# RC_Transmitter_TX_FINAL_v43.net
KiCad netlist of a schematic drawn in EAGLE
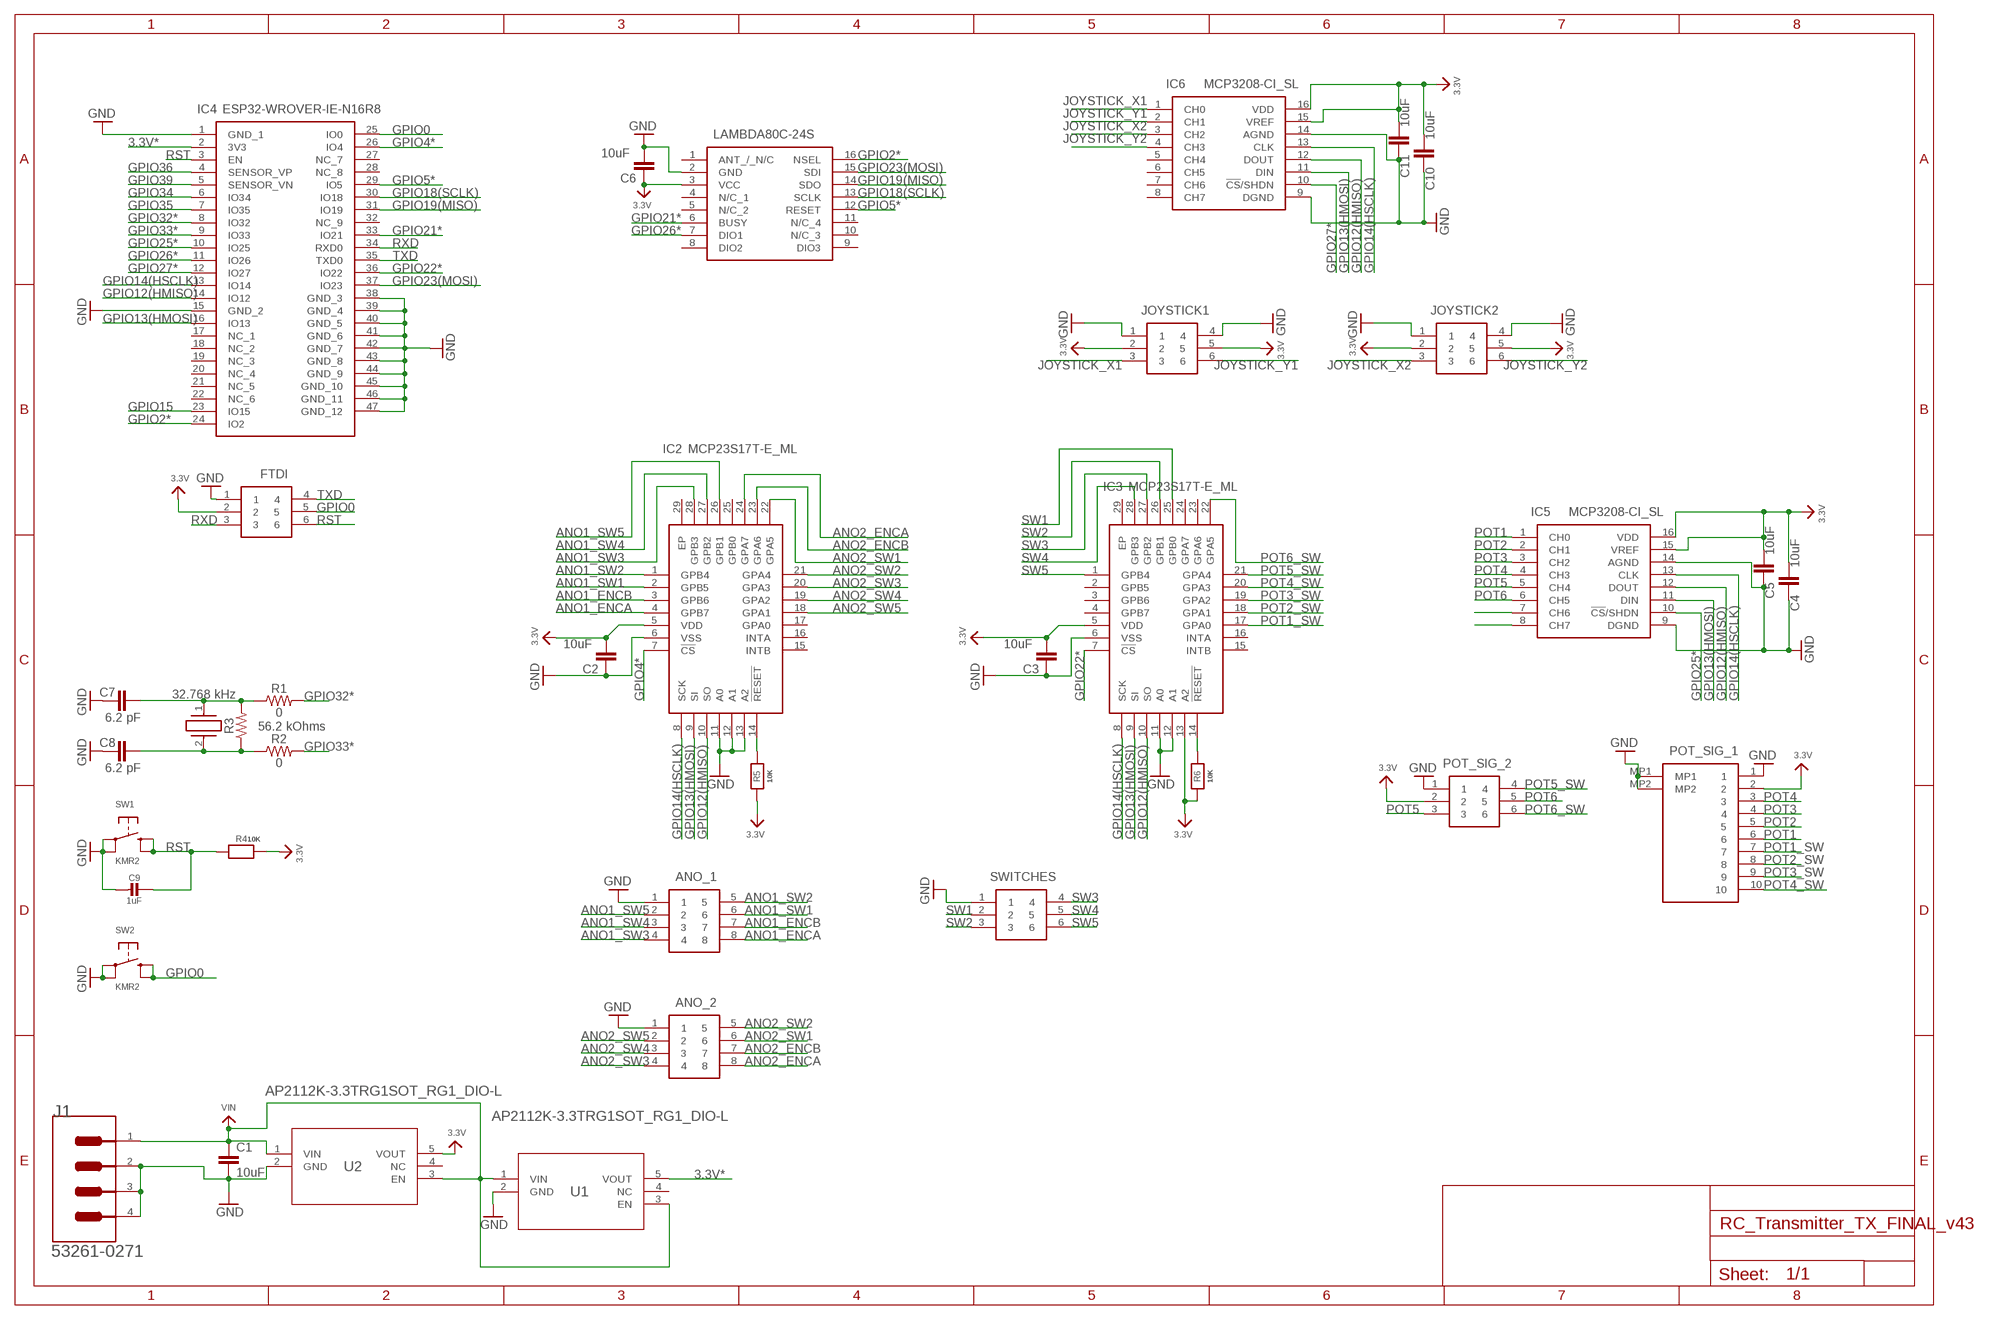
[diagram p0: schematic, sheet 1]

(export (version "E")
  (design (tool "Eeschema 10.0.6"))
  (components
    (comp (ref "ANO_1")
      (value "0532610871")
      (footprint "eagle-import:53261-0871")
      (libsource (lib "eagle-import") (part "0532610871"))
    )
    (comp (ref "ANO_2")
      (value "0532610871")
      (footprint "eagle-import:53261-0871")
      (libsource (lib "eagle-import") (part "0532610871"))
    )
    (comp (ref "C1")
      (value "10uF")
      (footprint "eagle-import:0805")
      (libsource (lib "eagle-import") (part "10UF-0805-10V-10%"))
    )
    (comp (ref "C2")
      (value "10uF")
      (footprint "eagle-import:0805")
      (libsource (lib "eagle-import") (part "10UF-0805-10V-10%"))
    )
    (comp (ref "C3")
      (value "10uF")
      (footprint "eagle-import:0805")
      (libsource (lib "eagle-import") (part "10UF-0805-10V-10%"))
    )
    (comp (ref "C4")
      (value "10uF")
      (footprint "eagle-import:0805")
      (libsource (lib "eagle-import") (part "10UF-0805-10V-10%"))
    )
    (comp (ref "C5")
      (value "10uF")
      (footprint "eagle-import:0805")
      (libsource (lib "eagle-import") (part "10UF-0805-10V-10%"))
    )
    (comp (ref "C6")
      (value "10uF")
      (footprint "eagle-import:0805")
      (libsource (lib "eagle-import") (part "10UF-0805-10V-10%"))
    )
    (comp (ref "C7")
      (value "6.2 pF")
      (footprint "eagle-import:CAPC2012X110")
      (libsource (lib "eagle-import") (part "CCHIP-0805(2012-METRIC)_"))
    )
    (comp (ref "C8")
      (value "6.2 pF")
      (footprint "eagle-import:CAPC2012X110")
      (libsource (lib "eagle-import") (part "CCHIP-0805(2012-METRIC)_"))
    )
    (comp (ref "C9")
      (value "1uF")
      (footprint "eagle-import:0805-NO")
      (libsource (lib "eagle-import") (part "CAP_CERAMIC0805-NOOUTLINE"))
    )
    (comp (ref "C10")
      (value "10uF")
      (footprint "eagle-import:0805")
      (libsource (lib "eagle-import") (part "10UF-0805-10V-10%"))
    )
    (comp (ref "C11")
      (value "10uF")
      (footprint "eagle-import:0805")
      (libsource (lib "eagle-import") (part "10UF-0805-10V-10%"))
    )
    (comp (ref "CRYSTAL")
      (value "32.768 kHz")
      (footprint "eagle-import:ECX327CDX1293")
      (fields
        (field (name "ARROW_PART_NUMBER") "ECX-.327-CDX-1293")
        (field (name "MOUSER_PART_NUMBER") "520-ECX-.327CDX-1293")
        (field (name "ARROW_PART_NUMBER_1") "Crystal")
      )
      (libsource (lib "eagle-import") (part "ECX-.327-CDX-1293"))
    )
    (comp (ref "FTDI")
      (value "0532610671")
      (footprint "eagle-import:0532610671")
      (libsource (lib "eagle-import") (part "0532610671"))
    )
    (comp (ref "IC1")
      (value "LAMBDA80C-24S")
      (footprint "eagle-import:LAMBDA80C24S")
      (fields (field (name "MOUSER_PART_NUMBER") "223-LAMBDA80C-24S"))
      (libsource (lib "eagle-import") (part "LAMBDA80C-24S"))
    )
    (comp (ref "IC2")
      (value "MCP23S17T-E_ML")
      (footprint "eagle-import:QFN65P600X600X100-29N")
      (fields
        (field (name "ARROW_PART_NUMBER") "MCP23S17T-E/ML")
        (field (name "MOUSER_PART_NUMBER") "579-MCP23S17T-E/ML")
      )
      (libsource (lib "eagle-import") (part "MCP23S17T-E_ML"))
    )
    (comp (ref "IC3")
      (value "MCP23S17T-E_ML")
      (footprint "eagle-import:QFN65P600X600X100-29N")
      (fields
        (field (name "ARROW_PART_NUMBER") "MCP23S17T-E/ML")
        (field (name "MOUSER_PART_NUMBER") "579-MCP23S17T-E/ML")
      )
      (libsource (lib "eagle-import") (part "MCP23S17T-E_ML"))
    )
    (comp (ref "IC4")
      (value "ESP32-WROVER-IE-N16R8")
      (footprint "eagle-import:ESP32WROVERIEN16R8")
      (fields
        (field (name "MANUFACTURER_PART_NUMBER") "ESP32-Wrover-IE-N16R8")
        (field (name "MOUSER_PART_NUMBER") "356-ESP32WRVIE2864UC")
      )
      (libsource (lib "eagle-import") (part "ESP32-WROVER-IE-N16R8"))
    )
    (comp (ref "IC5")
      (value "MCP3208-CI_SL")
      (footprint "eagle-import:SOIC127P600X175-16N")
      (fields
        (field (name "ARROW_PART_NUMBER") "MCP3208-CI/SL")
        (field (name "MOUSER_PART_NUMBER") "579-MCP3208CISL")
      )
      (libsource (lib "eagle-import") (part "MCP3208-CI_SL"))
    )
    (comp (ref "IC6")
      (value "MCP3208-CI_SL")
      (footprint "eagle-import:SOIC127P600X175-16N")
      (fields
        (field (name "ARROW_PART_NUMBER") "MCP3208-CI/SL")
        (field (name "MOUSER_PART_NUMBER") "579-MCP3208CISL")
      )
      (libsource (lib "eagle-import") (part "MCP3208-CI_SL"))
    )
    (comp (ref "J1")
      (value "MOLEX_53261-0271MOLEX_53261-0271_0_0")
      (footprint "eagle-import:MOLEX_53261-0271_0")
      (fields
        (field (name "DIGIKEY_PART_NUMBER") "WM7620CT-ND")
        (field (name "MF") "Molex")
        (field (name "MOUSER_PART_NUMBER") "538-53261-0271")
      )
      (libsource (lib "eagle-import") (part "MOLEX_53261-0271MOLEX_53261-0271_0_0"))
    )
    (comp (ref "JOYSTICK1")
      (value "0532610671")
      (footprint "eagle-import:0532610671")
      (libsource (lib "eagle-import") (part "0532610671"))
    )
    (comp (ref "JOYSTICK2")
      (value "0532610671")
      (footprint "eagle-import:0532610671")
      (libsource (lib "eagle-import") (part "0532610671"))
    )
    (comp (ref "POT_SIG_1")
      (value "0532611071")
      (footprint "eagle-import:0532611071")
      (libsource (lib "eagle-import") (part "0532611071"))
    )
    (comp (ref "POT_SIG_2")
      (value "0532610671")
      (footprint "eagle-import:0532610671")
      (libsource (lib "eagle-import") (part "0532610671"))
    )
    (comp (ref "R1")
      (value "0")
      (footprint "eagle-import:0603")
      (libsource (lib "eagle-import") (part "0OHM-0603-1/10W-5%"))
    )
    (comp (ref "R2")
      (value "0")
      (footprint "eagle-import:0603")
      (libsource (lib "eagle-import") (part "0OHM-0603-1/10W-5%"))
    )
    (comp (ref "R3")
      (value "56.2 kOhms")
      (footprint "eagle-import:0603")
      (libsource (lib "eagle-import") (part "0OHM-0603-1/10W-5%"))
    )
    (comp (ref "R4")
      (value "10K")
      (footprint "eagle-import:_0805")
      (libsource (lib "eagle-import") (part "RESISTOR_0805"))
    )
    (comp (ref "R5")
      (value "10K")
      (footprint "eagle-import:_0805")
      (libsource (lib "eagle-import") (part "RESISTOR_0805"))
    )
    (comp (ref "R6")
      (value "10K")
      (footprint "eagle-import:_0805")
      (libsource (lib "eagle-import") (part "RESISTOR_0805"))
    )
    (comp (ref "SW1")
      (value "KMR2")
      (footprint "eagle-import:BTN_KMR2_4.6X2.8")
      (libsource (lib "eagle-import") (part "SWITCH_TACT_SMT4.6X2.8"))
    )
    (comp (ref "SW2")
      (value "KMR2")
      (footprint "eagle-import:BTN_KMR2_4.6X2.8")
      (libsource (lib "eagle-import") (part "SWITCH_TACT_SMT4.6X2.8"))
    )
    (comp (ref "SWITCHES")
      (value "0532610671")
      (footprint "eagle-import:0532610671")
      (libsource (lib "eagle-import") (part "0532610671"))
    )
    (comp (ref "U1")
      (value "AP2112K-3.3TRG1SOT_RG1_DIO-L")
      (footprint "eagle-import:SOT_RG1_DIO-L")
      (fields
        (field (name "MANUFACTURER_PART_NUMBER") "AP2112K-3.3TRG1")
        (field (name "COPYRIGHT") "Copyright (C) 2023 Ultra Librarian. All rights reserved.")
      )
      (libsource (lib "eagle-import") (part "AP2112K-3.3TRG1SOT_RG1_DIO-L"))
    )
    (comp (ref "U2")
      (value "AP2112K-3.3TRG1SOT_RG1_DIO-L")
      (footprint "eagle-import:SOT_RG1_DIO-L")
      (fields
        (field (name "MANUFACTURER_PART_NUMBER") "AP2112K-3.3TRG1")
        (field (name "COPYRIGHT") "Copyright (C) 2023 Ultra Librarian. All rights reserved.")
      )
      (libsource (lib "eagle-import") (part "AP2112K-3.3TRG1SOT_RG1_DIO-L"))
    )
  )
  (nets
    (net (code "1") (name "/3.3V*") (class "Default")
      (node (ref "IC4") (pin "2") (pinfunction "3V3_2") (pintype "bidirectional"))
      (node (ref "U1") (pin "5") (pinfunction "VOUT_5") (pintype "passive"))
    )
    (net (code "2") (name "/ANO1_ENCA") (class "Default")
      (node (ref "ANO_1") (pin "8") (pinfunction "8_8") (pintype "bidirectional"))
      (node (ref "IC2") (pin "4") (pinfunction "GPB7_4") (pintype "bidirectional"))
    )
    (net (code "3") (name "/ANO1_ENCB") (class "Default")
      (node (ref "ANO_1") (pin "7") (pinfunction "7_7") (pintype "bidirectional"))
      (node (ref "IC2") (pin "3") (pinfunction "GPB6_3") (pintype "bidirectional"))
    )
    (net (code "4") (name "/ANO1_SW1") (class "Default")
      (node (ref "ANO_1") (pin "6") (pinfunction "6_6") (pintype "bidirectional"))
      (node (ref "IC2") (pin "2") (pinfunction "GPB5_2") (pintype "bidirectional"))
    )
    (net (code "5") (name "/ANO1_SW2") (class "Default")
      (node (ref "ANO_1") (pin "5") (pinfunction "5_5") (pintype "bidirectional"))
      (node (ref "IC2") (pin "1") (pinfunction "GPB4_1") (pintype "bidirectional"))
    )
    (net (code "6") (name "/ANO1_SW3") (class "Default")
      (node (ref "ANO_1") (pin "4") (pinfunction "4_4") (pintype "bidirectional"))
      (node (ref "IC2") (pin "28") (pinfunction "GPB3_28") (pintype "bidirectional"))
    )
    (net (code "7") (name "/ANO1_SW4") (class "Default")
      (node (ref "ANO_1") (pin "3") (pinfunction "3_3") (pintype "bidirectional"))
      (node (ref "IC2") (pin "27") (pinfunction "GPB2_27") (pintype "bidirectional"))
    )
    (net (code "8") (name "/ANO1_SW5") (class "Default")
      (node (ref "ANO_1") (pin "2") (pinfunction "2_2") (pintype "bidirectional"))
      (node (ref "IC2") (pin "26") (pinfunction "GPB1_26") (pintype "bidirectional"))
    )
    (net (code "9") (name "/ANO2_ENCA") (class "Default")
      (node (ref "ANO_2") (pin "8") (pinfunction "8_8") (pintype "bidirectional"))
      (node (ref "IC2") (pin "24") (pinfunction "GPA7_24") (pintype "bidirectional"))
    )
    (net (code "10") (name "/ANO2_ENCB") (class "Default")
      (node (ref "ANO_2") (pin "7") (pinfunction "7_7") (pintype "bidirectional"))
      (node (ref "IC2") (pin "23") (pinfunction "GPA6_23") (pintype "bidirectional"))
    )
    (net (code "11") (name "/ANO2_SW1") (class "Default")
      (node (ref "ANO_2") (pin "6") (pinfunction "6_6") (pintype "bidirectional"))
      (node (ref "IC2") (pin "22") (pinfunction "GPA5_22") (pintype "bidirectional"))
    )
    (net (code "12") (name "/ANO2_SW2") (class "Default")
      (node (ref "ANO_2") (pin "5") (pinfunction "5_5") (pintype "bidirectional"))
      (node (ref "IC2") (pin "21") (pinfunction "GPA4_21") (pintype "bidirectional"))
    )
    (net (code "13") (name "/ANO2_SW3") (class "Default")
      (node (ref "ANO_2") (pin "4") (pinfunction "4_4") (pintype "bidirectional"))
      (node (ref "IC2") (pin "20") (pinfunction "GPA3_20") (pintype "bidirectional"))
    )
    (net (code "14") (name "/ANO2_SW4") (class "Default")
      (node (ref "ANO_2") (pin "3") (pinfunction "3_3") (pintype "bidirectional"))
      (node (ref "IC2") (pin "19") (pinfunction "GPA2_19") (pintype "bidirectional"))
    )
    (net (code "15") (name "/ANO2_SW5") (class "Default")
      (node (ref "ANO_2") (pin "2") (pinfunction "2_2") (pintype "bidirectional"))
      (node (ref "IC2") (pin "18") (pinfunction "GPA1_18") (pintype "bidirectional"))
    )
    (net (code "16") (name "/GPIO0") (class "Default")
      (node (ref "FTDI") (pin "5") (pinfunction "5_5") (pintype "bidirectional"))
      (node (ref "IC4") (pin "25") (pinfunction "IO0_25") (pintype "bidirectional"))
      (node (ref "SW2") (pin "B") (pinfunction "S_B") (pintype "passive"))
      (node (ref "SW2") (pin "B'") (pinfunction "S1_B'") (pintype "passive"))
    )
    (net (code "17") (name "/GPIO2*") (class "Default")
      (node (ref "IC1") (pin "16") (pinfunction "NSEL_16") (pintype "bidirectional"))
      (node (ref "IC4") (pin "24") (pinfunction "IO2_24") (pintype "bidirectional"))
    )
    (net (code "18") (name "/GPIO4*") (class "Default")
      (node (ref "IC2") (pin "7") (pinfunction "~{CS}_7") (pintype "bidirectional"))
      (node (ref "IC4") (pin "26") (pinfunction "IO4_26") (pintype "bidirectional"))
    )
    (net (code "19") (name "/GPIO5*") (class "Default")
      (node (ref "IC1") (pin "12") (pinfunction "RESET_12") (pintype "bidirectional"))
      (node (ref "IC4") (pin "29") (pinfunction "IO5_29") (pintype "bidirectional"))
    )
    (net (code "20") (name "/GPIO12(HMISO)") (class "Default")
      (node (ref "IC2") (pin "10") (pinfunction "SO_10") (pintype "bidirectional"))
      (node (ref "IC3") (pin "10") (pinfunction "SO_10") (pintype "bidirectional"))
      (node (ref "IC4") (pin "14") (pinfunction "IO12_14") (pintype "bidirectional"))
      (node (ref "IC5") (pin "12") (pinfunction "DOUT_12") (pintype "bidirectional"))
      (node (ref "IC6") (pin "12") (pinfunction "DOUT_12") (pintype "bidirectional"))
    )
    (net (code "21") (name "/GPIO13(HMOSI)") (class "Default")
      (node (ref "IC2") (pin "9") (pinfunction "SI_9") (pintype "bidirectional"))
      (node (ref "IC3") (pin "9") (pinfunction "SI_9") (pintype "bidirectional"))
      (node (ref "IC4") (pin "16") (pinfunction "IO13_16") (pintype "bidirectional"))
      (node (ref "IC5") (pin "11") (pinfunction "DIN_11") (pintype "bidirectional"))
      (node (ref "IC6") (pin "11") (pinfunction "DIN_11") (pintype "bidirectional"))
    )
    (net (code "22") (name "/GPIO14(HSCLK)") (class "Default")
      (node (ref "IC2") (pin "8") (pinfunction "SCK_8") (pintype "bidirectional"))
      (node (ref "IC3") (pin "8") (pinfunction "SCK_8") (pintype "bidirectional"))
      (node (ref "IC4") (pin "13") (pinfunction "IO14_13") (pintype "bidirectional"))
      (node (ref "IC5") (pin "13") (pinfunction "CLK_13") (pintype "bidirectional"))
      (node (ref "IC6") (pin "13") (pinfunction "CLK_13") (pintype "bidirectional"))
    )
    (net (code "23") (name "/GPIO15") (class "Default")
      (node (ref "IC4") (pin "23") (pinfunction "IO15_23") (pintype "bidirectional"))
    )
    (net (code "24") (name "/GPIO18(SCLK)") (class "Default")
      (node (ref "IC1") (pin "13") (pinfunction "SCLK_13") (pintype "bidirectional"))
      (node (ref "IC4") (pin "30") (pinfunction "IO18_30") (pintype "bidirectional"))
    )
    (net (code "25") (name "/GPIO19(MISO)") (class "Default")
      (node (ref "IC1") (pin "14") (pinfunction "SDO_14") (pintype "bidirectional"))
      (node (ref "IC4") (pin "31") (pinfunction "IO19_31") (pintype "bidirectional"))
    )
    (net (code "26") (name "/GPIO21*") (class "Default")
      (node (ref "IC1") (pin "6") (pinfunction "BUSY_6") (pintype "bidirectional"))
      (node (ref "IC4") (pin "33") (pinfunction "IO21_33") (pintype "bidirectional"))
    )
    (net (code "27") (name "/GPIO22*") (class "Default")
      (node (ref "IC3") (pin "7") (pinfunction "~{CS}_7") (pintype "bidirectional"))
      (node (ref "IC4") (pin "36") (pinfunction "IO22_36") (pintype "bidirectional"))
    )
    (net (code "28") (name "/GPIO23(MOSI)") (class "Default")
      (node (ref "IC1") (pin "15") (pinfunction "SDI_15") (pintype "bidirectional"))
      (node (ref "IC4") (pin "37") (pinfunction "IO23_37") (pintype "bidirectional"))
    )
    (net (code "29") (name "/GPIO25*") (class "Default")
      (node (ref "IC4") (pin "10") (pinfunction "IO25_10") (pintype "bidirectional"))
      (node (ref "IC5") (pin "10") (pinfunction "~{CS}/SHDN_10") (pintype "bidirectional"))
    )
    (net (code "30") (name "/GPIO26*") (class "Default")
      (node (ref "IC1") (pin "7") (pinfunction "DIO1_7") (pintype "bidirectional"))
      (node (ref "IC4") (pin "11") (pinfunction "IO26_11") (pintype "bidirectional"))
    )
    (net (code "31") (name "/GPIO27*") (class "Default")
      (node (ref "IC4") (pin "12") (pinfunction "IO27_12") (pintype "bidirectional"))
      (node (ref "IC6") (pin "10") (pinfunction "~{CS}/SHDN_10") (pintype "bidirectional"))
    )
    (net (code "32") (name "/GPIO32*") (class "Default")
      (node (ref "IC4") (pin "8") (pinfunction "IO32_8") (pintype "bidirectional"))
      (node (ref "R1") (pin "2") (pinfunction "2_2") (pintype "passive"))
    )
    (net (code "33") (name "/GPIO33*") (class "Default")
      (node (ref "IC4") (pin "9") (pinfunction "IO33_9") (pintype "bidirectional"))
      (node (ref "R2") (pin "2") (pinfunction "2_2") (pintype "passive"))
    )
    (net (code "34") (name "/GPIO34") (class "Default")
      (node (ref "IC4") (pin "6") (pinfunction "IO34_6") (pintype "bidirectional"))
    )
    (net (code "35") (name "/GPIO35") (class "Default")
      (node (ref "IC4") (pin "7") (pinfunction "IO35_7") (pintype "bidirectional"))
    )
    (net (code "36") (name "/GPIO36") (class "Default")
      (node (ref "IC4") (pin "4") (pinfunction "SENSOR_VP_4") (pintype "bidirectional"))
    )
    (net (code "37") (name "/GPIO39") (class "Default")
      (node (ref "IC4") (pin "5") (pinfunction "SENSOR_VN_5") (pintype "bidirectional"))
    )
    (net (code "38") (name "/JOYSTICK_X1") (class "Default")
      (node (ref "IC6") (pin "1") (pinfunction "CH0_1") (pintype "bidirectional"))
      (node (ref "JOYSTICK1") (pin "3") (pinfunction "3_3") (pintype "bidirectional"))
    )
    (net (code "39") (name "/JOYSTICK_X2") (class "Default")
      (node (ref "IC6") (pin "3") (pinfunction "CH2_3") (pintype "bidirectional"))
      (node (ref "JOYSTICK2") (pin "3") (pinfunction "3_3") (pintype "bidirectional"))
    )
    (net (code "40") (name "/JOYSTICK_Y1") (class "Default")
      (node (ref "IC6") (pin "2") (pinfunction "CH1_2") (pintype "bidirectional"))
      (node (ref "JOYSTICK1") (pin "6") (pinfunction "6_6") (pintype "bidirectional"))
    )
    (net (code "41") (name "/JOYSTICK_Y2") (class "Default")
      (node (ref "IC6") (pin "4") (pinfunction "CH3_4") (pintype "bidirectional"))
      (node (ref "JOYSTICK2") (pin "6") (pinfunction "6_6") (pintype "bidirectional"))
    )
    (net (code "42") (name "/POT1") (class "Default")
      (node (ref "IC5") (pin "1") (pinfunction "CH0_1") (pintype "bidirectional"))
      (node (ref "POT_SIG_1") (pin "6") (pinfunction "6_6") (pintype "bidirectional"))
    )
    (net (code "43") (name "/POT1_SW") (class "Default")
      (node (ref "IC3") (pin "17") (pinfunction "GPA0_17") (pintype "bidirectional"))
      (node (ref "POT_SIG_1") (pin "7") (pinfunction "7_7") (pintype "bidirectional"))
    )
    (net (code "44") (name "/POT2") (class "Default")
      (node (ref "IC5") (pin "2") (pinfunction "CH1_2") (pintype "bidirectional"))
      (node (ref "POT_SIG_1") (pin "5") (pinfunction "5_5") (pintype "bidirectional"))
    )
    (net (code "45") (name "/POT2_SW") (class "Default")
      (node (ref "IC3") (pin "18") (pinfunction "GPA1_18") (pintype "bidirectional"))
      (node (ref "POT_SIG_1") (pin "8") (pinfunction "8_8") (pintype "bidirectional"))
    )
    (net (code "46") (name "/POT3") (class "Default")
      (node (ref "IC5") (pin "3") (pinfunction "CH2_3") (pintype "bidirectional"))
      (node (ref "POT_SIG_1") (pin "4") (pinfunction "4_4") (pintype "bidirectional"))
    )
    (net (code "47") (name "/POT3_SW") (class "Default")
      (node (ref "IC3") (pin "19") (pinfunction "GPA2_19") (pintype "bidirectional"))
      (node (ref "POT_SIG_1") (pin "9") (pinfunction "9_9") (pintype "bidirectional"))
    )
    (net (code "48") (name "/POT4") (class "Default")
      (node (ref "IC5") (pin "4") (pinfunction "CH3_4") (pintype "bidirectional"))
      (node (ref "POT_SIG_1") (pin "3") (pinfunction "3_3") (pintype "bidirectional"))
    )
    (net (code "49") (name "/POT4_SW") (class "Default")
      (node (ref "IC3") (pin "20") (pinfunction "GPA3_20") (pintype "bidirectional"))
      (node (ref "POT_SIG_1") (pin "10") (pinfunction "10_10") (pintype "bidirectional"))
    )
    (net (code "50") (name "/POT5") (class "Default")
      (node (ref "IC5") (pin "5") (pinfunction "CH4_5") (pintype "bidirectional"))
      (node (ref "POT_SIG_2") (pin "3") (pinfunction "3_3") (pintype "bidirectional"))
    )
    (net (code "51") (name "/POT5_SW") (class "Default")
      (node (ref "IC3") (pin "21") (pinfunction "GPA4_21") (pintype "bidirectional"))
      (node (ref "POT_SIG_2") (pin "4") (pinfunction "4_4") (pintype "bidirectional"))
    )
    (net (code "52") (name "/POT6") (class "Default")
      (node (ref "IC5") (pin "6") (pinfunction "CH5_6") (pintype "bidirectional"))
      (node (ref "POT_SIG_2") (pin "5") (pinfunction "5_5") (pintype "bidirectional"))
    )
    (net (code "53") (name "/POT6_SW") (class "Default")
      (node (ref "IC3") (pin "22") (pinfunction "GPA5_22") (pintype "bidirectional"))
      (node (ref "POT_SIG_2") (pin "6") (pinfunction "6_6") (pintype "bidirectional"))
    )
    (net (code "54") (name "/RST") (class "Default")
      (node (ref "C9") (pin "1") (pinfunction "1_1") (pintype "passive"))
      (node (ref "FTDI") (pin "6") (pinfunction "6_6") (pintype "bidirectional"))
      (node (ref "IC4") (pin "3") (pinfunction "EN_3") (pintype "bidirectional"))
      (node (ref "R4") (pin "1") (pinfunction "1_1") (pintype "passive"))
      (node (ref "SW1") (pin "B") (pinfunction "S_B") (pintype "passive"))
      (node (ref "SW1") (pin "B'") (pinfunction "S1_B'") (pintype "passive"))
    )
    (net (code "55") (name "/RXD") (class "Default")
      (node (ref "FTDI") (pin "3") (pinfunction "3_3") (pintype "bidirectional"))
      (node (ref "IC4") (pin "34") (pinfunction "RXD0_34") (pintype "bidirectional"))
    )
    (net (code "56") (name "/SW1") (class "Default")
      (node (ref "IC3") (pin "25") (pinfunction "GPB0_25") (pintype "bidirectional"))
      (node (ref "SWITCHES") (pin "2") (pinfunction "2_2") (pintype "bidirectional"))
    )
    (net (code "57") (name "/SW2") (class "Default")
      (node (ref "IC3") (pin "26") (pinfunction "GPB1_26") (pintype "bidirectional"))
      (node (ref "SWITCHES") (pin "3") (pinfunction "3_3") (pintype "bidirectional"))
    )
    (net (code "58") (name "/SW3") (class "Default")
      (node (ref "IC3") (pin "27") (pinfunction "GPB2_27") (pintype "bidirectional"))
      (node (ref "SWITCHES") (pin "4") (pinfunction "4_4") (pintype "bidirectional"))
    )
    (net (code "59") (name "/SW4") (class "Default")
      (node (ref "IC3") (pin "28") (pinfunction "GPB3_28") (pintype "bidirectional"))
      (node (ref "SWITCHES") (pin "5") (pinfunction "5_5") (pintype "bidirectional"))
    )
    (net (code "60") (name "/SW5") (class "Default")
      (node (ref "IC3") (pin "1") (pinfunction "GPB4_1") (pintype "bidirectional"))
      (node (ref "SWITCHES") (pin "6") (pinfunction "6_6") (pintype "bidirectional"))
    )
    (net (code "61") (name "/TXD") (class "Default")
      (node (ref "FTDI") (pin "4") (pinfunction "4_4") (pintype "bidirectional"))
      (node (ref "IC4") (pin "35") (pinfunction "TXD0_35") (pintype "bidirectional"))
    )
    (net (code "62") (name "3.3V") (class "Default")
      (node (ref "C10") (pin "2") (pinfunction "2_2") (pintype "passive"))
      (node (ref "C11") (pin "2") (pinfunction "2_2") (pintype "passive"))
      (node (ref "C2") (pin "2") (pinfunction "2_2") (pintype "passive"))
      (node (ref "C3") (pin "2") (pinfunction "2_2") (pintype "passive"))
      (node (ref "C4") (pin "2") (pinfunction "2_2") (pintype "passive"))
      (node (ref "C5") (pin "2") (pinfunction "2_2") (pintype "passive"))
      (node (ref "C6") (pin "1") (pinfunction "1_1") (pintype "passive"))
      (node (ref "FTDI") (pin "2") (pinfunction "2_2") (pintype "bidirectional"))
      (node (ref "IC1") (pin "3") (pinfunction "VCC_3") (pintype "bidirectional"))
      (node (ref "IC2") (pin "5") (pinfunction "VDD_5") (pintype "bidirectional"))
      (node (ref "IC3") (pin "13") (pinfunction "A2_13") (pintype "bidirectional"))
      (node (ref "IC3") (pin "5") (pinfunction "VDD_5") (pintype "bidirectional"))
      (node (ref "IC5") (pin "15") (pinfunction "VREF_15") (pintype "bidirectional"))
      (node (ref "IC5") (pin "16") (pinfunction "VDD_16") (pintype "bidirectional"))
      (node (ref "IC6") (pin "15") (pinfunction "VREF_15") (pintype "bidirectional"))
      (node (ref "IC6") (pin "16") (pinfunction "VDD_16") (pintype "bidirectional"))
      (node (ref "JOYSTICK1") (pin "2") (pinfunction "2_2") (pintype "bidirectional"))
      (node (ref "JOYSTICK1") (pin "5") (pinfunction "5_5") (pintype "bidirectional"))
      (node (ref "JOYSTICK2") (pin "2") (pinfunction "2_2") (pintype "bidirectional"))
      (node (ref "JOYSTICK2") (pin "5") (pinfunction "5_5") (pintype "bidirectional"))
      (node (ref "POT_SIG_1") (pin "2") (pinfunction "2_2") (pintype "bidirectional"))
      (node (ref "POT_SIG_2") (pin "2") (pinfunction "2_2") (pintype "bidirectional"))
      (node (ref "R4") (pin "2") (pinfunction "2_2") (pintype "passive"))
      (node (ref "R5") (pin "1") (pinfunction "1_1") (pintype "passive"))
      (node (ref "R6") (pin "1") (pinfunction "1_1") (pintype "passive"))
      (node (ref "U2") (pin "5") (pinfunction "VOUT_5") (pintype "passive"))
    )
    (net (code "63") (name "GND") (class "Default")
      (node (ref "ANO_1") (pin "1") (pinfunction "1_1") (pintype "bidirectional"))
      (node (ref "ANO_2") (pin "1") (pinfunction "1_1") (pintype "bidirectional"))
      (node (ref "C1") (pin "2") (pinfunction "2_2") (pintype "passive"))
      (node (ref "C10") (pin "1") (pinfunction "1_1") (pintype "passive"))
      (node (ref "C11") (pin "1") (pinfunction "1_1") (pintype "passive"))
      (node (ref "C2") (pin "1") (pinfunction "1_1") (pintype "passive"))
      (node (ref "C3") (pin "1") (pinfunction "1_1") (pintype "passive"))
      (node (ref "C4") (pin "1") (pinfunction "1_1") (pintype "passive"))
      (node (ref "C5") (pin "1") (pinfunction "1_1") (pintype "passive"))
      (node (ref "C6") (pin "2") (pinfunction "2_2") (pintype "passive"))
      (node (ref "C7") (pin "1") (pinfunction "1_1") (pintype "passive"))
      (node (ref "C8") (pin "1") (pinfunction "1_1") (pintype "passive"))
      (node (ref "C9") (pin "2") (pinfunction "2_2") (pintype "passive"))
      (node (ref "FTDI") (pin "1") (pinfunction "1_1") (pintype "bidirectional"))
      (node (ref "IC1") (pin "2") (pinfunction "GND_2") (pintype "bidirectional"))
      (node (ref "IC2") (pin "11") (pinfunction "A0_11") (pintype "bidirectional"))
      (node (ref "IC2") (pin "12") (pinfunction "A1_12") (pintype "bidirectional"))
      (node (ref "IC2") (pin "13") (pinfunction "A2_13") (pintype "bidirectional"))
      (node (ref "IC2") (pin "6") (pinfunction "VSS_6") (pintype "bidirectional"))
      (node (ref "IC3") (pin "11") (pinfunction "A0_11") (pintype "bidirectional"))
      (node (ref "IC3") (pin "12") (pinfunction "A1_12") (pintype "bidirectional"))
      (node (ref "IC3") (pin "6") (pinfunction "VSS_6") (pintype "bidirectional"))
      (node (ref "IC4") (pin "1") (pinfunction "GND_1_1") (pintype "bidirectional"))
      (node (ref "IC4") (pin "15") (pinfunction "GND_2_15") (pintype "bidirectional"))
      (node (ref "IC4") (pin "38") (pinfunction "GND_3_38") (pintype "bidirectional"))
      (node (ref "IC4") (pin "39") (pinfunction "GND_4_39") (pintype "bidirectional"))
      (node (ref "IC4") (pin "40") (pinfunction "GND_5_40") (pintype "bidirectional"))
      (node (ref "IC4") (pin "41") (pinfunction "GND_6_41") (pintype "bidirectional"))
      (node (ref "IC4") (pin "42") (pinfunction "GND_7_42") (pintype "bidirectional"))
      (node (ref "IC4") (pin "43") (pinfunction "GND_8_43") (pintype "bidirectional"))
      (node (ref "IC4") (pin "44") (pinfunction "GND_9_44") (pintype "bidirectional"))
      (node (ref "IC4") (pin "45") (pinfunction "GND_10_45") (pintype "bidirectional"))
      (node (ref "IC4") (pin "46") (pinfunction "GND_11_46") (pintype "bidirectional"))
      (node (ref "IC4") (pin "47") (pinfunction "GND_12_47") (pintype "bidirectional"))
      (node (ref "IC5") (pin "14") (pinfunction "AGND_14") (pintype "bidirectional"))
      (node (ref "IC5") (pin "9") (pinfunction "DGND_9") (pintype "bidirectional"))
      (node (ref "IC6") (pin "14") (pinfunction "AGND_14") (pintype "bidirectional"))
      (node (ref "IC6") (pin "9") (pinfunction "DGND_9") (pintype "bidirectional"))
      (node (ref "J1") (pin "2") (pinfunction "2_2") (pintype "bidirectional"))
      (node (ref "J1") (pin "3") (pinfunction "MNT_1_3") (pintype "bidirectional"))
      (node (ref "J1") (pin "4") (pinfunction "MNT_2_4") (pintype "bidirectional"))
      (node (ref "JOYSTICK1") (pin "1") (pinfunction "1_1") (pintype "bidirectional"))
      (node (ref "JOYSTICK1") (pin "4") (pinfunction "4_4") (pintype "bidirectional"))
      (node (ref "JOYSTICK2") (pin "1") (pinfunction "1_1") (pintype "bidirectional"))
      (node (ref "JOYSTICK2") (pin "4") (pinfunction "4_4") (pintype "bidirectional"))
      (node (ref "POT_SIG_1") (pin "1") (pinfunction "1_1") (pintype "bidirectional"))
      (node (ref "POT_SIG_1") (pin "MP1") (pinfunction "MP1_MP1") (pintype "bidirectional"))
      (node (ref "POT_SIG_1") (pin "MP2") (pinfunction "MP2_MP2") (pintype "bidirectional"))
      (node (ref "POT_SIG_2") (pin "1") (pinfunction "1_1") (pintype "bidirectional"))
      (node (ref "SW1") (pin "A") (pinfunction "P_A") (pintype "passive"))
      (node (ref "SW1") (pin "A'") (pinfunction "P1_A'") (pintype "passive"))
      (node (ref "SW2") (pin "A") (pinfunction "P_A") (pintype "passive"))
      (node (ref "SW2") (pin "A'") (pinfunction "P1_A'") (pintype "passive"))
      (node (ref "SWITCHES") (pin "1") (pinfunction "1_1") (pintype "bidirectional"))
      (node (ref "U1") (pin "2") (pinfunction "GND_2") (pintype "passive"))
      (node (ref "U2") (pin "2") (pinfunction "GND_2") (pintype "passive"))
    )
    (net (code "64") (name "Net-(CRYSTAL-X1)") (class "Default")
      (node (ref "C7") (pin "2") (pinfunction "2_2") (pintype "passive"))
      (node (ref "CRYSTAL") (pin "1") (pinfunction "X1_1") (pintype "bidirectional"))
      (node (ref "R1") (pin "1") (pinfunction "1_1") (pintype "passive"))
      (node (ref "R3") (pin "2") (pinfunction "2_2") (pintype "passive"))
    )
    (net (code "65") (name "Net-(CRYSTAL-X2)") (class "Default")
      (node (ref "C8") (pin "2") (pinfunction "2_2") (pintype "passive"))
      (node (ref "CRYSTAL") (pin "2") (pinfunction "X2_2") (pintype "bidirectional"))
      (node (ref "R2") (pin "1") (pinfunction "1_1") (pintype "passive"))
      (node (ref "R3") (pin "1") (pinfunction "1_1") (pintype "passive"))
    )
    (net (code "66") (name "Net-(IC2-~{RESET})") (class "Default")
      (node (ref "IC2") (pin "14") (pinfunction "~{RESET}_14") (pintype "bidirectional"))
      (node (ref "R5") (pin "2") (pinfunction "2_2") (pintype "passive"))
    )
    (net (code "67") (name "Net-(IC3-~{RESET})") (class "Default")
      (node (ref "IC3") (pin "14") (pinfunction "~{RESET}_14") (pintype "bidirectional"))
      (node (ref "R6") (pin "2") (pinfunction "2_2") (pintype "passive"))
    )
    (net (code "68") (name "VIN") (class "Default")
      (node (ref "C1") (pin "1") (pinfunction "1_1") (pintype "passive"))
      (node (ref "J1") (pin "1") (pinfunction "1_1") (pintype "bidirectional"))
      (node (ref "U1") (pin "1") (pinfunction "VIN_1") (pintype "passive"))
      (node (ref "U1") (pin "3") (pinfunction "EN_3") (pintype "passive"))
      (node (ref "U2") (pin "1") (pinfunction "VIN_1") (pintype "passive"))
      (node (ref "U2") (pin "3") (pinfunction "EN_3") (pintype "passive"))
    )
    (net (code "69") (name "unconnected-(IC1-ANT_{slash}_N{slash}C-Pad1)") (class "Default")
      (node (ref "IC1") (pin "1") (pinfunction "ANT_/_N/C_1") (pintype "bidirectional"))
    )
    (net (code "70") (name "unconnected-(IC1-DIO2-Pad8)") (class "Default")
      (node (ref "IC1") (pin "8") (pinfunction "DIO2_8") (pintype "bidirectional"))
    )
    (net (code "71") (name "unconnected-(IC1-DIO3-Pad9)") (class "Default")
      (node (ref "IC1") (pin "9") (pinfunction "DIO3_9") (pintype "bidirectional"))
    )
    (net (code "72") (name "unconnected-(IC1-N{slash}C_1-Pad4)") (class "Default")
      (node (ref "IC1") (pin "4") (pinfunction "N/C_1_4") (pintype "bidirectional"))
    )
    (net (code "73") (name "unconnected-(IC1-N{slash}C_2-Pad5)") (class "Default")
      (node (ref "IC1") (pin "5") (pinfunction "N/C_2_5") (pintype "bidirectional"))
    )
    (net (code "74") (name "unconnected-(IC1-N{slash}C_3-Pad10)") (class "Default")
      (node (ref "IC1") (pin "10") (pinfunction "N/C_3_10") (pintype "bidirectional"))
    )
    (net (code "75") (name "unconnected-(IC1-N{slash}C_4-Pad11)") (class "Default")
      (node (ref "IC1") (pin "11") (pinfunction "N/C_4_11") (pintype "bidirectional"))
    )
    (net (code "76") (name "unconnected-(IC2-EP-Pad29)") (class "Default")
      (node (ref "IC2") (pin "29") (pinfunction "EP_29") (pintype "bidirectional"))
    )
    (net (code "77") (name "unconnected-(IC2-GPA0-Pad17)") (class "Default")
      (node (ref "IC2") (pin "17") (pinfunction "GPA0_17") (pintype "bidirectional"))
    )
    (net (code "78") (name "unconnected-(IC2-GPB0-Pad25)") (class "Default")
      (node (ref "IC2") (pin "25") (pinfunction "GPB0_25") (pintype "bidirectional"))
    )
    (net (code "79") (name "unconnected-(IC2-INTA-Pad16)") (class "Default")
      (node (ref "IC2") (pin "16") (pinfunction "INTA_16") (pintype "bidirectional"))
    )
    (net (code "80") (name "unconnected-(IC2-INTB-Pad15)") (class "Default")
      (node (ref "IC2") (pin "15") (pinfunction "INTB_15") (pintype "bidirectional"))
    )
    (net (code "81") (name "unconnected-(IC3-EP-Pad29)") (class "Default")
      (node (ref "IC3") (pin "29") (pinfunction "EP_29") (pintype "bidirectional"))
    )
    (net (code "82") (name "unconnected-(IC3-GPA6-Pad23)") (class "Default")
      (node (ref "IC3") (pin "23") (pinfunction "GPA6_23") (pintype "bidirectional"))
    )
    (net (code "83") (name "unconnected-(IC3-GPA7-Pad24)") (class "Default")
      (node (ref "IC3") (pin "24") (pinfunction "GPA7_24") (pintype "bidirectional"))
    )
    (net (code "84") (name "unconnected-(IC3-GPB5-Pad2)") (class "Default")
      (node (ref "IC3") (pin "2") (pinfunction "GPB5_2") (pintype "bidirectional"))
    )
    (net (code "85") (name "unconnected-(IC3-GPB6-Pad3)") (class "Default")
      (node (ref "IC3") (pin "3") (pinfunction "GPB6_3") (pintype "bidirectional"))
    )
    (net (code "86") (name "unconnected-(IC3-GPB7-Pad4)") (class "Default")
      (node (ref "IC3") (pin "4") (pinfunction "GPB7_4") (pintype "bidirectional"))
    )
    (net (code "87") (name "unconnected-(IC3-INTA-Pad16)") (class "Default")
      (node (ref "IC3") (pin "16") (pinfunction "INTA_16") (pintype "bidirectional"))
    )
    (net (code "88") (name "unconnected-(IC3-INTB-Pad15)") (class "Default")
      (node (ref "IC3") (pin "15") (pinfunction "INTB_15") (pintype "bidirectional"))
    )
    (net (code "89") (name "unconnected-(IC4-NC_1-Pad17)") (class "Default")
      (node (ref "IC4") (pin "17") (pinfunction "NC_1_17") (pintype "bidirectional"))
    )
    (net (code "90") (name "unconnected-(IC4-NC_2-Pad18)") (class "Default")
      (node (ref "IC4") (pin "18") (pinfunction "NC_2_18") (pintype "bidirectional"))
    )
    (net (code "91") (name "unconnected-(IC4-NC_3-Pad19)") (class "Default")
      (node (ref "IC4") (pin "19") (pinfunction "NC_3_19") (pintype "bidirectional"))
    )
    (net (code "92") (name "unconnected-(IC4-NC_4-Pad20)") (class "Default")
      (node (ref "IC4") (pin "20") (pinfunction "NC_4_20") (pintype "bidirectional"))
    )
    (net (code "93") (name "unconnected-(IC4-NC_5-Pad21)") (class "Default")
      (node (ref "IC4") (pin "21") (pinfunction "NC_5_21") (pintype "bidirectional"))
    )
    (net (code "94") (name "unconnected-(IC4-NC_6-Pad22)") (class "Default")
      (node (ref "IC4") (pin "22") (pinfunction "NC_6_22") (pintype "bidirectional"))
    )
    (net (code "95") (name "unconnected-(IC4-NC_7-Pad27)") (class "Default")
      (node (ref "IC4") (pin "27") (pinfunction "NC_7_27") (pintype "bidirectional"))
    )
    (net (code "96") (name "unconnected-(IC4-NC_8-Pad28)") (class "Default")
      (node (ref "IC4") (pin "28") (pinfunction "NC_8_28") (pintype "bidirectional"))
    )
    (net (code "97") (name "unconnected-(IC4-NC_9-Pad32)") (class "Default")
      (node (ref "IC4") (pin "32") (pinfunction "NC_9_32") (pintype "bidirectional"))
    )
    (net (code "98") (name "unconnected-(IC5-CH6-Pad7)") (class "Default")
      (node (ref "IC5") (pin "7") (pinfunction "CH6_7") (pintype "bidirectional"))
    )
    (net (code "99") (name "unconnected-(IC5-CH7-Pad8)") (class "Default")
      (node (ref "IC5") (pin "8") (pinfunction "CH7_8") (pintype "bidirectional"))
    )
    (net (code "100") (name "unconnected-(IC6-CH4-Pad5)") (class "Default")
      (node (ref "IC6") (pin "5") (pinfunction "CH4_5") (pintype "bidirectional"))
    )
    (net (code "101") (name "unconnected-(IC6-CH5-Pad6)") (class "Default")
      (node (ref "IC6") (pin "6") (pinfunction "CH5_6") (pintype "bidirectional"))
    )
    (net (code "102") (name "unconnected-(IC6-CH6-Pad7)") (class "Default")
      (node (ref "IC6") (pin "7") (pinfunction "CH6_7") (pintype "bidirectional"))
    )
    (net (code "103") (name "unconnected-(IC6-CH7-Pad8)") (class "Default")
      (node (ref "IC6") (pin "8") (pinfunction "CH7_8") (pintype "bidirectional"))
    )
    (net (code "104") (name "unconnected-(U1-NC-Pad4)") (class "Default")
      (node (ref "U1") (pin "4") (pinfunction "NC_4") (pintype "passive"))
    )
    (net (code "105") (name "unconnected-(U2-NC-Pad4)") (class "Default")
      (node (ref "U2") (pin "4") (pinfunction "NC_4") (pintype "passive"))
    )
  )
)
